# power_and_comms.net
KiCad netlist of a schematic drawn in Altium Designer
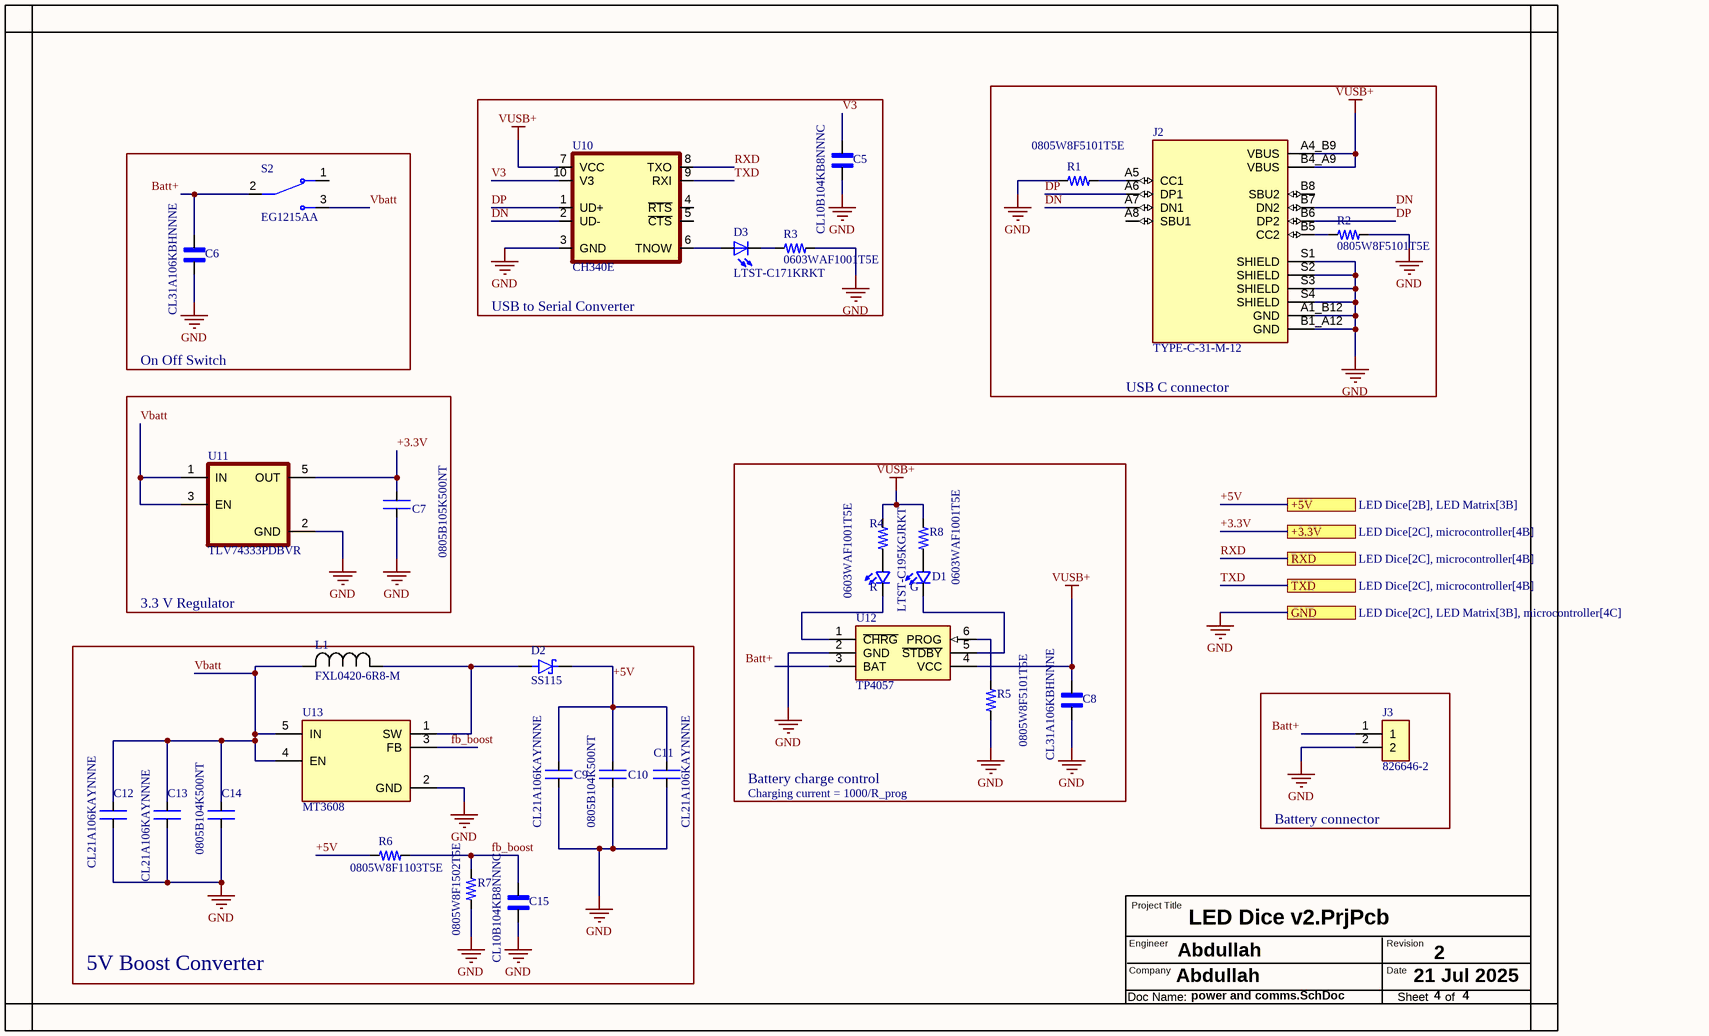
[diagram p0: power and comms.SchDoc]

(export (version "E")
  (design (tool "Eeschema 10.0.6"))
  (components
    (comp (ref "C5")
      (value "CL10B104KB8NNNC")
      (footprint "CAPC1608X90N")
      (description "0.1ÂµF Â±10% 50V Ceramic Capacitor X7R 0603 _1608 Metric_")
      (fields (field (name "MF") "Samsung Electro-Mechanics"))
      (libsource (lib "Cap 0603 MLCC") (part "CL10B104KB8NNNC"))
    )
    (comp (ref "C6")
      (value "CL31A106KBHNNNE")
      (footprint "WCAP-CSGP_885012208060")
      (description "50V 10uF X5R ±10% 1206 Multilayer Ceramic Capacitors MLCC - SMD/SMT ROHS")
      (fields (field (name "MP") "885012208060"))
      (libsource (lib "CAP 1206 MLCC") (part "CL31A106KBHNNNE"))
    )
    (comp (ref "C7")
      (value "0805B105K500NT")
      (footprint "CAPC2012X135N")
      (description "50V 1uF X7R ±10% 0805 Multilayer Ceramic Capacitors MLCC - SMD/SMT ROHS")
      (libsource (lib "Cap 0805 MLCC") (part "0805B105K500NT"))
    )
    (comp (ref "C8")
      (value "CL31A106KBHNNNE")
      (footprint "WCAP-CSGP_885012208060")
      (description "50V 10uF X5R ±10% 1206 Multilayer Ceramic Capacitors MLCC - SMD/SMT ROHS")
      (fields (field (name "MP") "885012208060"))
      (libsource (lib "CAP 1206 MLCC") (part "CL31A106KBHNNNE"))
    )
    (comp (ref "C9")
      (value "CL21A106KAYNNNE")
      (footprint "CAPC2012X135N")
      (description "25V 10uF X5R ±10% 0805 Multilayer Ceramic Capacitors MLCC - SMD/SMT ROHS")
      (fields (field (name "MP") "CL31A106KPHNNNE"))
      (libsource (lib "Cap 0805 MLCC") (part "CL21A106KAYNNNE"))
    )
    (comp (ref "C10")
      (value "CL21A106KAYNNNE")
      (footprint "CAPC2012X135N")
      (description "25V 10uF X5R ±10% 0805 Multilayer Ceramic Capacitors MLCC - SMD/SMT ROHS")
      (fields (field (name "MP") "CL31A106KPHNNNE"))
      (libsource (lib "Cap 0805 MLCC") (part "CL21A106KAYNNNE"))
    )
    (comp (ref "C11")
      (value "0805B104K500NT")
      (footprint "CAPC2012X135N")
      (description "50V 100nF X7R ±10% 0805 Multilayer Ceramic Capacitors MLCC - SMD/SMT ROHS")
      (libsource (lib "Cap 0805 MLCC") (part "0805B104K500NT"))
    )
    (comp (ref "C12")
      (value "CL21A106KAYNNNE")
      (footprint "CAPC2012X135N")
      (description "25V 10uF X5R ±10% 0805 Multilayer Ceramic Capacitors MLCC - SMD/SMT ROHS")
      (fields (field (name "MP") "CL31A106KPHNNNE"))
      (libsource (lib "Cap 0805 MLCC") (part "CL21A106KAYNNNE"))
    )
    (comp (ref "C13")
      (value "CL21A106KAYNNNE")
      (footprint "CAPC2012X135N")
      (description "25V 10uF X5R ±10% 0805 Multilayer Ceramic Capacitors MLCC - SMD/SMT ROHS")
      (fields (field (name "MP") "CL31A106KPHNNNE"))
      (libsource (lib "Cap 0805 MLCC") (part "CL21A106KAYNNNE"))
    )
    (comp (ref "C14")
      (value "0805B104K500NT")
      (footprint "CAPC2012X135N")
      (description "50V 100nF X7R ±10% 0805 Multilayer Ceramic Capacitors MLCC - SMD/SMT ROHS")
      (libsource (lib "Cap 0805 MLCC") (part "0805B104K500NT"))
    )
    (comp (ref "C15")
      (value "CL10B104KB8NNNC")
      (footprint "CAPC1608X90N")
      (description "0.1ÂµF Â±10% 50V Ceramic Capacitor X7R 0603 _1608 Metric_")
      (fields (field (name "MF") "Samsung Electro-Mechanics"))
      (libsource (lib "Cap 0603 MLCC") (part "CL10B104KB8NNNC"))
    )
    (comp (ref "D1")
      (value "LTST-C195KGJRKT")
      (footprint "LTST-BILED-15X16")
      (description "Green, Red 571nm Green, 631nm Red LED Indication - Discrete 2V Green, 2V Red 0606 (1616 Metric)")
      (fields (field (name "MF") "Lite-On Inc."))
      (libsource (lib "LTST-C195KGJRKT") (part "LTST-C195KGJRKT"))
    )
    (comp (ref "D2")
      (value "SS115")
      (footprint "DIOM4325X250N")
      (description "1A, 150V, Schottky Rectifier")
      (fields (field (name "MF") "Taiwan Semiconductor"))
      (libsource (lib "SS115") (part "SS115"))
    )
    (comp (ref "D3")
      (value "LTST-C171KRKT")
      (footprint "DIOC200X125X110")
      (description "Red LED  0805 _2012 Indication 631nm - Discrete 2V 0805 _2012 Metric_")
      (fields (field (name "MF") "Lite-On Inc."))
      (libsource (lib "LTST-C171KRKT") (part "LTST-C171KRKT"))
    )
    (comp (ref "J2")
      (value "TYPE-C-31-M-12")
      (footprint "HRO_TYPE-C-31-M-12")
      (description "USB Connectors 24 Receptacle 1 8.94*7.3mm RoHS")
      (fields (field (name "MF") "HRO Electronics Co., Ltd."))
      (libsource (lib "TYPE-C-31-M-12") (part "TYPE-C-31-M-12"))
    )
    (comp (ref "J3")
      (value "826646-2")
      (footprint "TE_826646-2")
      (description "Conn Unshrouded Header HDR 2 POS 2.54mm Solder ST Thru-Hole")
      (fields (field (name "MF") "TE Connectivity"))
      (libsource (lib "826646-2") (part "826646-2"))
    )
    (comp (ref "L1")
      (value "FXL0420-6R8-M")
      (footprint "IND_FXL0420_CMT")
      (description "Description")
      (fields (field (name "COPYRIGHT") "Copyright (C) 2025 Ultra Librarian. All rights reserved."))
      (libsource (lib "FXL0420-6R8-M") (part "FXL0420-6R8-M"))
    )
    (comp (ref "R1")
      (value "0805W8F5101T5E")
      (footprint "RESC2012X65N")
      (description "5.1kΩ 0805  125mW Thick Film Resistors 150V ±100ppm/℃ ±1% Chip Resistor - Surface Mount ROHS")
      (libsource (lib "RES 0805") (part "0805W8F5101T5E"))
    )
    (comp (ref "R2")
      (value "0805W8F5101T5E")
      (footprint "RESC2012X65N")
      (description "5.1kΩ 0805  125mW Thick Film Resistors 150V ±100ppm/℃ ±1% Chip Resistor - Surface Mount ROHS")
      (libsource (lib "RES 0805") (part "0805W8F5101T5E"))
    )
    (comp (ref "R3")
      (value "0603WAF1001T5E")
      (footprint "RESC1508X60N")
      (description "1kΩ 0603 100mW Thick Film Resistors 75V ±100ppm/℃ ±1%  Chip Resistor - Surface Mount ROHS")
      (libsource (lib "CRT0603-PW-1002ELF") (part "0603WAF1001T5E"))
    )
    (comp (ref "R4")
      (value "0603WAF1001T5E")
      (footprint "RESC1508X60N")
      (description "1kΩ 0603 100mW Thick Film Resistors 75V ±100ppm/℃ ±1%  Chip Resistor - Surface Mount ROHS")
      (libsource (lib "CRT0603-PW-1002ELF") (part "0603WAF1001T5E"))
    )
    (comp (ref "R5")
      (value "0805W8F5101T5E")
      (footprint "RESC2012X65N")
      (description "5.1kΩ 0805  125mW Thick Film Resistors 150V ±100ppm/℃ ±1% Chip Resistor - Surface Mount ROHS")
      (libsource (lib "RES 0805") (part "0805W8F5101T5E"))
    )
    (comp (ref "R6")
      (value "0805W8F1103T5E")
      (footprint "RESC2012X65N")
      (description "110kΩ 0805  125mW Thick Film Resistors 150V ±100ppm/℃ ±1% Chip Resistor - Surface Mount ROHS")
      (libsource (lib "CRT0805-BW-1002ELF") (part "0805W8F1103T5E"))
    )
    (comp (ref "R7")
      (value "0805W8F1502T5E")
      (footprint "RESC2012X65N")
      (description "15kΩ 0805  125mW Thick Film Resistors 150V ±100ppm/℃ ±1% Chip Resistor - Surface Mount ROHS")
      (libsource (lib "CRT0805-BW-1002ELF") (part "0805W8F1502T5E"))
    )
    (comp (ref "R8")
      (value "0603WAF1001T5E")
      (footprint "RESC1508X60N")
      (description "1kΩ 0603 100mW Thick Film Resistors 75V ±100ppm/℃ ±1%  Chip Resistor - Surface Mount ROHS")
      (libsource (lib "CRT0603-PW-1002ELF") (part "0603WAF1001T5E"))
    )
    (comp (ref "S2")
      (value "EG1215AA")
      (footprint "SW_EG1215AA")
      (description "Slide Switch SPDT Surface Mount, Right Angle")
      (fields (field (name "MF") "E-Switch"))
      (libsource (lib "EG1215AA") (part "EG1215AA"))
    )
    (comp (ref "U10")
      (value "CH340E")
      (footprint "MSOP10")
      (description "USB to serial chip CH340")
      (fields (field (name "MF") "WCH"))
      (libsource (lib "CH340E") (part "CH340E"))
    )
    (comp (ref "U11")
      (value "TLV74333PDBVR")
      (footprint "SOT95P280X145-5N")
      (fields (field (name "MF") "Texas Instruments") (field (name "MP") "TLV74330PDBVR"))
      (libsource (lib "TLV74333PDBVR") (part "TLV74333PDBVR"))
    )
    (comp (ref "U12")
      (value "TP4057")
      (footprint "SOT23-6")
      (description "500mA linear li-ion battery charger TP4057 actual charge current to 500ma,")
      (fields (field (name "MF") "toppower"))
      (libsource (lib "TP4057") (part "TP4057"))
    )
    (comp (ref "U13")
      (value "MT3608")
      (footprint "SOT95P280X145-6N")
      (description "High Efficiency 1.2MHz2A Step Up Converter")
      (fields (field (name "MF") "Aerosemi Technology Co., Ltd"))
      (libsource (lib "MT3608") (part "MT3608"))
    )
  )
  (nets
    (net (code "1") (name "/+3.3V") (class "Default")
      (node (ref "C7") (pin "1") (pinfunction "A_1") (pintype "passive"))
      (node (ref "U11") (pin "5") (pinfunction "OUT_5") (pintype "passive"))
    )
    (net (code "2") (name "/+5V") (class "Default")
      (node (ref "C10") (pin "2") (pinfunction "C_2") (pintype "passive"))
      (node (ref "C11") (pin "1") (pinfunction "A_1") (pintype "passive"))
      (node (ref "C9") (pin "2") (pinfunction "C_2") (pintype "passive"))
      (node (ref "D2") (pin "C") (pinfunction "K_C") (pintype "passive"))
      (node (ref "R6") (pin "2") (pinfunction "2_2") (pintype "passive"))
    )
    (net (code "3") (name "/Batt+") (class "Default")
      (node (ref "C6") (pin "2") (pinfunction "2_2") (pintype "passive"))
      (node (ref "J3") (pin "1") (pinfunction "1_1") (pintype "passive"))
      (node (ref "S2") (pin "2") (pinfunction "2_2") (pintype "passive"))
      (node (ref "U12") (pin "3") (pinfunction "BAT_3") (pintype "power_in"))
    )
    (net (code "4") (name "/DN") (class "Default")
      (node (ref "J2") (pin "A7") (pinfunction "DN1_A7") (pintype "bidirectional"))
      (node (ref "J2") (pin "B7") (pinfunction "DN2_B7") (pintype "bidirectional"))
      (node (ref "U10") (pin "2") (pinfunction "UD-_2") (pintype "bidirectional"))
    )
    (net (code "5") (name "/DP") (class "Default")
      (node (ref "J2") (pin "A6") (pinfunction "DP1_A6") (pintype "bidirectional"))
      (node (ref "J2") (pin "B6") (pinfunction "DP2_B6") (pintype "bidirectional"))
      (node (ref "U10") (pin "1") (pinfunction "UD+_1") (pintype "bidirectional"))
    )
    (net (code "6") (name "/RXD") (class "Default")
      (node (ref "U10") (pin "8") (pinfunction "TXO_8") (pintype "bidirectional"))
    )
    (net (code "7") (name "/TXD") (class "Default")
      (node (ref "U10") (pin "9") (pinfunction "RXI_9") (pintype "bidirectional"))
    )
    (net (code "8") (name "/V3") (class "Default")
      (node (ref "C5") (pin "2") (pinfunction "2_2") (pintype "passive"))
      (node (ref "U10") (pin "10") (pinfunction "V3_10") (pintype "bidirectional"))
    )
    (net (code "9") (name "/Vbatt") (class "Default")
      (node (ref "C12") (pin "2") (pinfunction "C_2") (pintype "passive"))
      (node (ref "C13") (pin "2") (pinfunction "C_2") (pintype "passive"))
      (node (ref "C14") (pin "1") (pinfunction "A_1") (pintype "passive"))
      (node (ref "L1") (pin "2") (pinfunction "2_2") (pintype "passive"))
      (node (ref "S2") (pin "3") (pinfunction "3_3") (pintype "passive"))
      (node (ref "U11") (pin "1") (pinfunction "IN_1") (pintype "passive"))
      (node (ref "U11") (pin "3") (pinfunction "EN_3") (pintype "passive"))
      (node (ref "U13") (pin "4") (pinfunction "EN_4") (pintype "passive"))
      (node (ref "U13") (pin "5") (pinfunction "IN_5") (pintype "passive"))
    )
    (net (code "10") (name "/fb_boost") (class "Default")
      (node (ref "C15") (pin "2") (pinfunction "2_2") (pintype "passive"))
      (node (ref "R6") (pin "1") (pinfunction "1_1") (pintype "passive"))
      (node (ref "R7") (pin "2") (pinfunction "2_2") (pintype "passive"))
      (node (ref "U13") (pin "3") (pinfunction "FB_3") (pintype "passive"))
    )
    (net (code "11") (name "GND") (class "Default")
      (node (ref "C10") (pin "1") (pinfunction "A_1") (pintype "passive"))
      (node (ref "C11") (pin "2") (pinfunction "C_2") (pintype "passive"))
      (node (ref "C12") (pin "1") (pinfunction "A_1") (pintype "passive"))
      (node (ref "C13") (pin "1") (pinfunction "A_1") (pintype "passive"))
      (node (ref "C14") (pin "2") (pinfunction "C_2") (pintype "passive"))
      (node (ref "C15") (pin "1") (pinfunction "1_1") (pintype "passive"))
      (node (ref "C5") (pin "1") (pinfunction "1_1") (pintype "passive"))
      (node (ref "C6") (pin "1") (pinfunction "1_1") (pintype "passive"))
      (node (ref "C7") (pin "2") (pinfunction "C_2") (pintype "passive"))
      (node (ref "C8") (pin "1") (pinfunction "1_1") (pintype "passive"))
      (node (ref "C9") (pin "1") (pinfunction "A_1") (pintype "passive"))
      (node (ref "J2") (pin "A1_B12") (pinfunction "GND_A1_B12") (pintype "power_in"))
      (node (ref "J2") (pin "B1_A12") (pinfunction "GND_B1_A12") (pintype "power_in"))
      (node (ref "J2") (pin "S1") (pinfunction "SHIELD_S1") (pintype "passive"))
      (node (ref "J2") (pin "S2") (pinfunction "SHIELD_S2") (pintype "passive"))
      (node (ref "J2") (pin "S3") (pinfunction "SHIELD_S3") (pintype "passive"))
      (node (ref "J2") (pin "S4") (pinfunction "SHIELD_S4") (pintype "passive"))
      (node (ref "J3") (pin "2") (pinfunction "2_2") (pintype "passive"))
      (node (ref "R1") (pin "2") (pinfunction "2_2") (pintype "passive"))
      (node (ref "R2") (pin "1") (pinfunction "1_1") (pintype "passive"))
      (node (ref "R3") (pin "2") (pinfunction "2_2") (pintype "passive"))
      (node (ref "R5") (pin "1") (pinfunction "1_1") (pintype "passive"))
      (node (ref "R7") (pin "1") (pinfunction "1_1") (pintype "passive"))
      (node (ref "U10") (pin "3") (pinfunction "GND_3") (pintype "bidirectional"))
      (node (ref "U11") (pin "2") (pinfunction "GND_2") (pintype "passive"))
      (node (ref "U12") (pin "2") (pinfunction "GND_2") (pintype "power_in"))
      (node (ref "U13") (pin "2") (pinfunction "GND_2") (pintype "power_in"))
    )
    (net (code "12") (name "Net-(D1-A1)") (class "Default")
      (node (ref "D1") (pin "P$1") (pinfunction "A1_P$1") (pintype "passive"))
      (node (ref "R8") (pin "1") (pinfunction "1_1") (pintype "passive"))
    )
    (net (code "13") (name "Net-(D1-A2)") (class "Default")
      (node (ref "D1") (pin "P$2") (pinfunction "A2_P$2") (pintype "passive"))
      (node (ref "R4") (pin "1") (pinfunction "1_1") (pintype "passive"))
    )
    (net (code "14") (name "Net-(D1-K1)") (class "Default")
      (node (ref "D1") (pin "P$3") (pinfunction "K1_P$3") (pintype "passive"))
      (node (ref "U12") (pin "5") (pinfunction "~{STDBY}_5") (pintype "open_collector"))
    )
    (net (code "15") (name "Net-(D1-K2)") (class "Default")
      (node (ref "D1") (pin "P$4") (pinfunction "K2_P$4") (pintype "passive"))
      (node (ref "U12") (pin "1") (pinfunction "~{CHRG}_1") (pintype "open_collector"))
    )
    (net (code "16") (name "Net-(D3-PadNEG)") (class "Default")
      (node (ref "D3") (pin "NEG") (pinfunction "NEG_NEG") (pintype "passive"))
      (node (ref "R3") (pin "1") (pinfunction "1_1") (pintype "passive"))
    )
    (net (code "17") (name "Net-(J2-CC1)") (class "Default")
      (node (ref "J2") (pin "A5") (pinfunction "CC1_A5") (pintype "bidirectional"))
      (node (ref "R1") (pin "1") (pinfunction "1_1") (pintype "passive"))
    )
    (net (code "18") (name "Net-(J2-CC2)") (class "Default")
      (node (ref "J2") (pin "B5") (pinfunction "CC2_B5") (pintype "bidirectional"))
      (node (ref "R2") (pin "2") (pinfunction "2_2") (pintype "passive"))
    )
    (net (code "19") (name "Net-(U10-TNOW)") (class "Default")
      (node (ref "D3") (pin "POS") (pinfunction "POS_POS") (pintype "passive"))
      (node (ref "U10") (pin "6") (pinfunction "TNOW_6") (pintype "bidirectional"))
    )
    (net (code "20") (name "Net-(U12-PROG)") (class "Default")
      (node (ref "R5") (pin "2") (pinfunction "2_2") (pintype "passive"))
      (node (ref "U12") (pin "6") (pinfunction "PROG_6") (pintype "input"))
    )
    (net (code "21") (name "Net-(U13-SW)") (class "Default")
      (node (ref "D2") (pin "A") (pinfunction "A_A") (pintype "passive"))
      (node (ref "L1") (pin "1") (pinfunction "1_1") (pintype "passive"))
      (node (ref "U13") (pin "1") (pinfunction "SW_1") (pintype "passive"))
    )
    (net (code "22") (name "VUSB+") (class "Default")
      (node (ref "C8") (pin "2") (pinfunction "2_2") (pintype "passive"))
      (node (ref "J2") (pin "A4_B9") (pinfunction "VBUS_A4_B9") (pintype "power_in"))
      (node (ref "J2") (pin "B4_A9") (pinfunction "VBUS_B4_A9") (pintype "power_in"))
      (node (ref "R4") (pin "2") (pinfunction "2_2") (pintype "passive"))
      (node (ref "R8") (pin "2") (pinfunction "2_2") (pintype "passive"))
      (node (ref "U10") (pin "7") (pinfunction "VCC_7") (pintype "bidirectional"))
      (node (ref "U12") (pin "4") (pinfunction "VCC_4") (pintype "power_in"))
    )
    (net (code "23") (name "unconnected-(J2-SBU1-PadA8)") (class "Default")
      (node (ref "J2") (pin "A8") (pinfunction "SBU1_A8") (pintype "bidirectional"))
    )
    (net (code "24") (name "unconnected-(J2-SBU2-PadB8)") (class "Default")
      (node (ref "J2") (pin "B8") (pinfunction "SBU2_B8") (pintype "bidirectional"))
    )
    (net (code "25") (name "unconnected-(S2-Pad1)") (class "Default")
      (node (ref "S2") (pin "1") (pinfunction "1_1") (pintype "passive"))
    )
    (net (code "26") (name "unconnected-(U10-~{CTS}-Pad5)") (class "Default")
      (node (ref "U10") (pin "5") (pinfunction "~{CTS}_5") (pintype "bidirectional"))
    )
    (net (code "27") (name "unconnected-(U10-~{RTS}-Pad4)") (class "Default")
      (node (ref "U10") (pin "4") (pinfunction "~{RTS}_4") (pintype "bidirectional"))
    )
  )
)
